# IotaWatt4_3.net
KiCad netlist of a schematic drawn in EAGLE
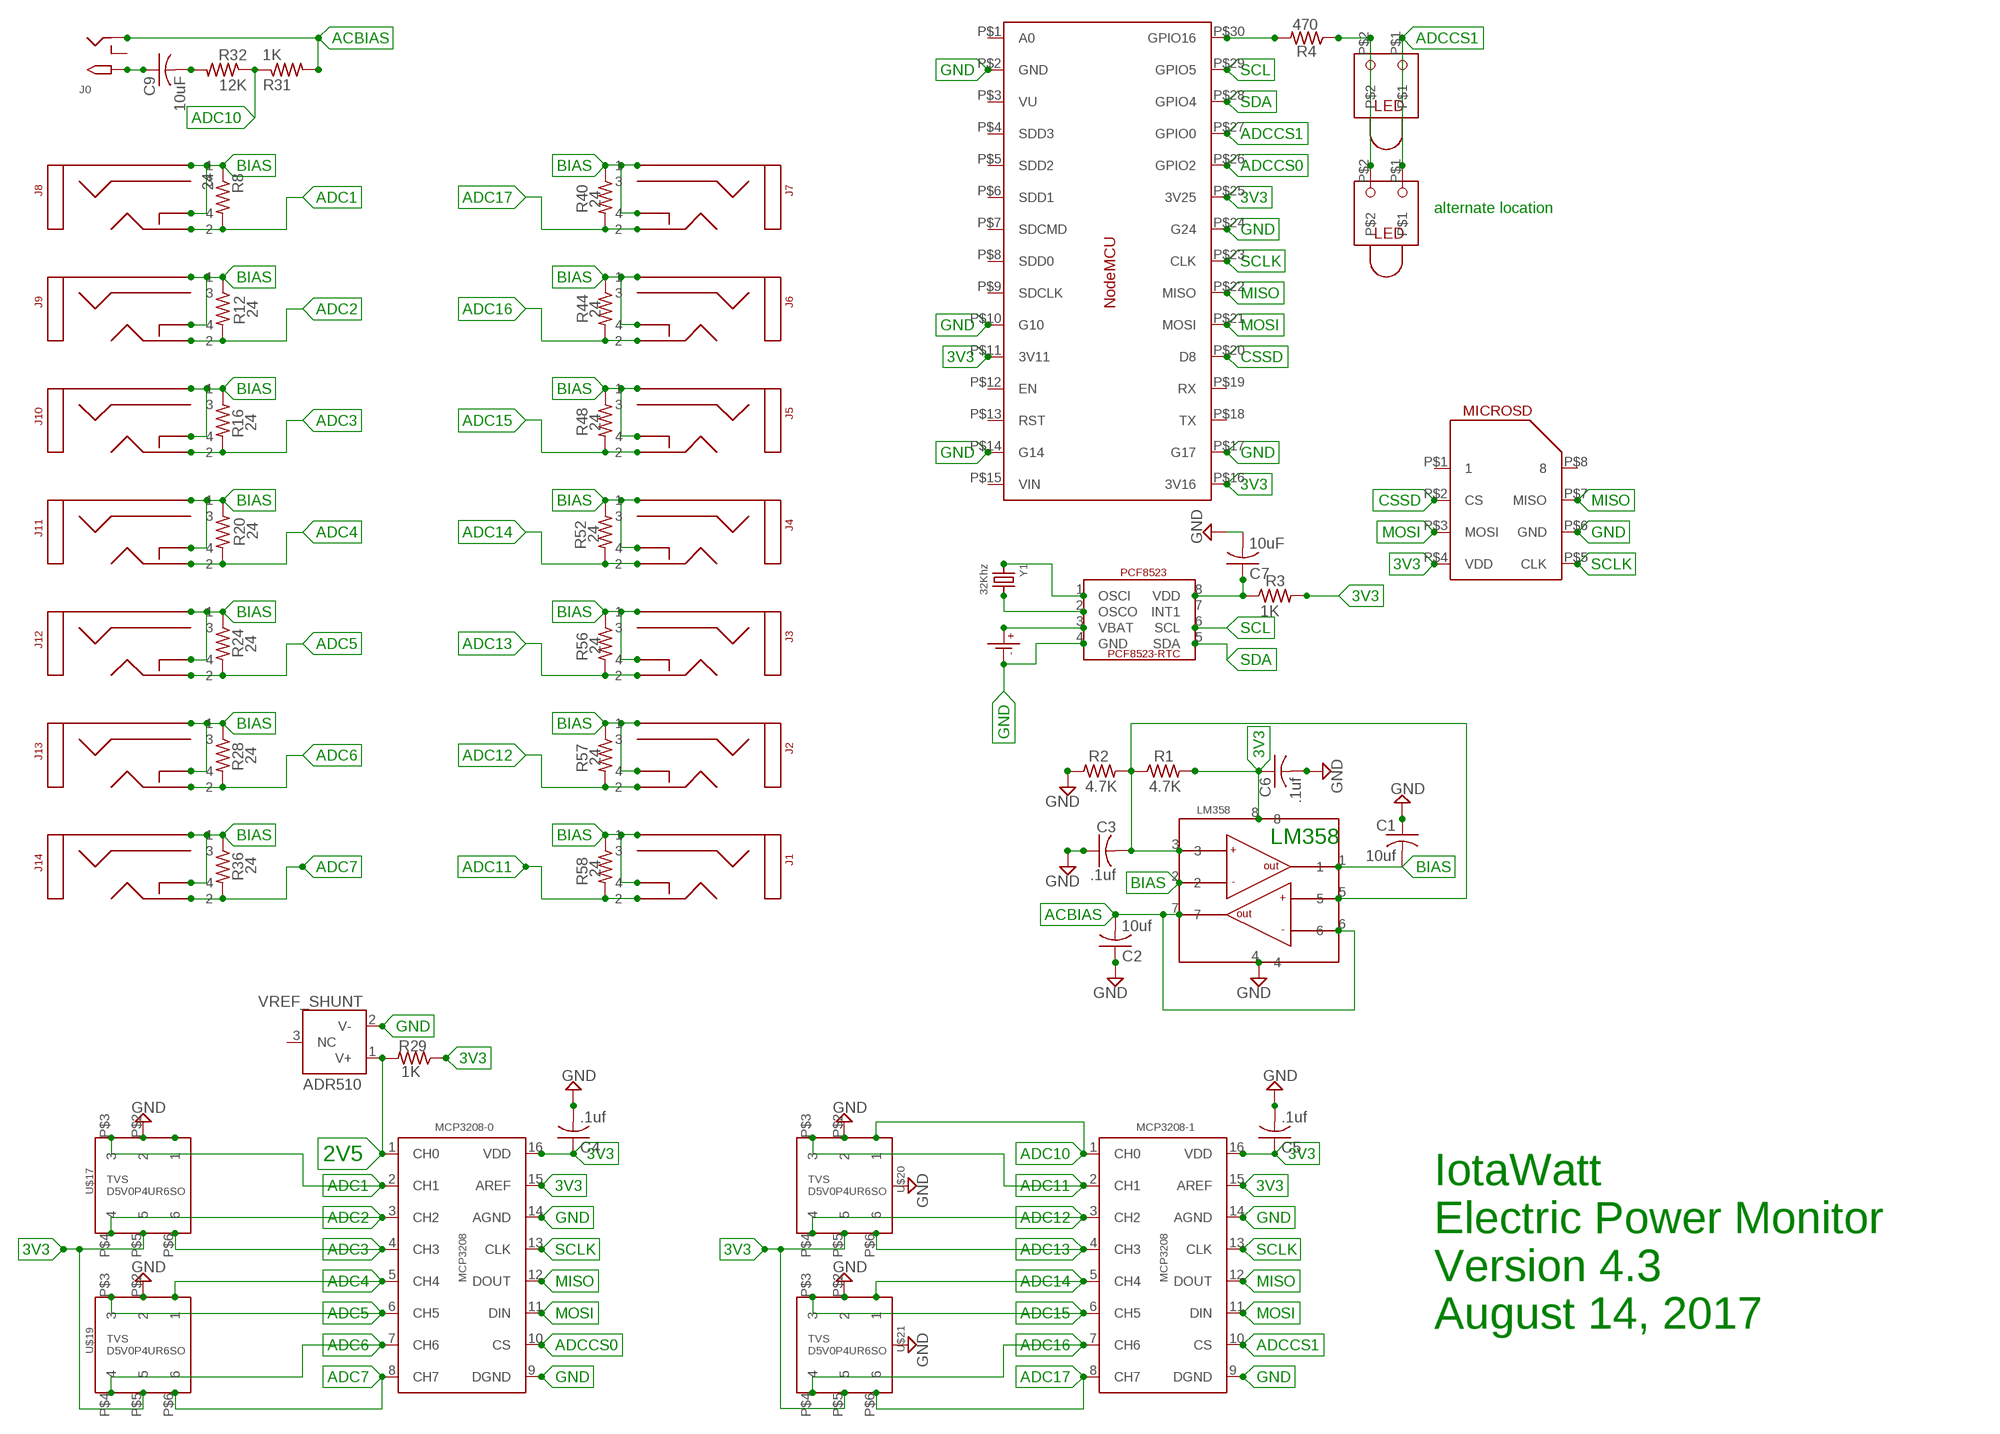
[diagram p0: schematic, sheet 1]

(export (version "E")
  (design (tool "Eeschema 10.0.6"))
  (components
    (comp (ref "ADR510")
      (value "VREF_SHUNT")
      (footprint "eagle-import:SOT23_3")
      (libsource (lib "eagle-import") (part "VREF_SHUNT"))
    )
    (comp (ref "C1")
      (value "10uf")
      (footprint "eagle-import:C0805")
      (libsource (lib "eagle-import") (part "C-USC0805"))
    )
    (comp (ref "C2")
      (value "10uf")
      (footprint "eagle-import:C0805")
      (libsource (lib "eagle-import") (part "C-USC0805"))
    )
    (comp (ref "C3")
      (value ".1uf")
      (footprint "eagle-import:C0805")
      (libsource (lib "eagle-import") (part "C-USC0805"))
    )
    (comp (ref "C4")
      (value ".1uf")
      (footprint "eagle-import:C0805")
      (libsource (lib "eagle-import") (part "C-USC0805"))
    )
    (comp (ref "C5")
      (value ".1uf")
      (footprint "eagle-import:C0805")
      (libsource (lib "eagle-import") (part "C-USC0805"))
    )
    (comp (ref "C6")
      (value ".1uf")
      (footprint "eagle-import:C0805")
      (libsource (lib "eagle-import") (part "C-USC0805"))
    )
    (comp (ref "C7")
      (value "10uF")
      (footprint "eagle-import:C0805")
      (libsource (lib "eagle-import") (part "C-USC0805"))
    )
    (comp (ref "C9")
      (value "10uF")
      (footprint "eagle-import:C0805")
      (libsource (lib "eagle-import") (part "C-USC0805"))
    )
    (comp (ref "J0")
      (value "2.1MMJACKSMT")
      (footprint "eagle-import:DCJACK_2MM_SMT")
      (libsource (lib "eagle-import") (part "2.1MMJACKSMT"))
    )
    (comp (ref "J1")
      (value "STEREO_SMD")
      (footprint "eagle-import:STEREO_SMT")
      (libsource (lib "eagle-import") (part "STEREO_SMD"))
    )
    (comp (ref "J2")
      (value "STEREO_SMD")
      (footprint "eagle-import:STEREO_SMT")
      (libsource (lib "eagle-import") (part "STEREO_SMD"))
    )
    (comp (ref "J3")
      (value "STEREO_SMD")
      (footprint "eagle-import:STEREO_SMT")
      (libsource (lib "eagle-import") (part "STEREO_SMD"))
    )
    (comp (ref "J4")
      (value "STEREO_SMD")
      (footprint "eagle-import:STEREO_SMT")
      (libsource (lib "eagle-import") (part "STEREO_SMD"))
    )
    (comp (ref "J5")
      (value "STEREO_SMD")
      (footprint "eagle-import:STEREO_SMT")
      (libsource (lib "eagle-import") (part "STEREO_SMD"))
    )
    (comp (ref "J6")
      (value "STEREO_SMD")
      (footprint "eagle-import:STEREO_SMT")
      (libsource (lib "eagle-import") (part "STEREO_SMD"))
    )
    (comp (ref "J7")
      (value "STEREO_SMD")
      (footprint "eagle-import:STEREO_SMT")
      (libsource (lib "eagle-import") (part "STEREO_SMD"))
    )
    (comp (ref "J8")
      (value "STEREO_SMD")
      (footprint "eagle-import:STEREO_SMT")
      (libsource (lib "eagle-import") (part "STEREO_SMD"))
    )
    (comp (ref "J9")
      (value "STEREO_SMD")
      (footprint "eagle-import:STEREO_SMT")
      (libsource (lib "eagle-import") (part "STEREO_SMD"))
    )
    (comp (ref "J10")
      (value "STEREO_SMD")
      (footprint "eagle-import:STEREO_SMT")
      (libsource (lib "eagle-import") (part "STEREO_SMD"))
    )
    (comp (ref "J11")
      (value "STEREO_SMD")
      (footprint "eagle-import:STEREO_SMT")
      (libsource (lib "eagle-import") (part "STEREO_SMD"))
    )
    (comp (ref "J12")
      (value "STEREO_SMD")
      (footprint "eagle-import:STEREO_SMT")
      (libsource (lib "eagle-import") (part "STEREO_SMD"))
    )
    (comp (ref "J13")
      (value "STEREO_SMD")
      (footprint "eagle-import:STEREO_SMT")
      (libsource (lib "eagle-import") (part "STEREO_SMD"))
    )
    (comp (ref "J14")
      (value "STEREO_SMD")
      (footprint "eagle-import:STEREO_SMT")
      (libsource (lib "eagle-import") (part "STEREO_SMD"))
    )
    (comp (ref "MCP3208-0")
      (value "MCP3208")
      (footprint "eagle-import:SOIC_16")
      (libsource (lib "eagle-import") (part "MCP3208"))
    )
    (comp (ref "MCP3208-1")
      (value "MCP3208")
      (footprint "eagle-import:SOIC_16")
      (libsource (lib "eagle-import") (part "MCP3208"))
    )
    (comp (ref "MICROSD")
      (value "MICROSD_PUSH/PULL")
      (footprint "eagle-import:MICROSD")
      (libsource (lib "eagle-import") (part "MICROSD_PUSH/PULL"))
    )
    (comp (ref "PCF8523")
      (value "PCF8523_RTC")
      (footprint "eagle-import:SOIC_8")
      (libsource (lib "eagle-import") (part "PCF8523_RTC"))
    )
    (comp (ref "R1")
      (value "4.7K")
      (footprint "eagle-import:R0805")
      (libsource (lib "eagle-import") (part "R-US_R0805"))
    )
    (comp (ref "R2")
      (value "4.7K")
      (footprint "eagle-import:R0805")
      (libsource (lib "eagle-import") (part "R-US_R0805"))
    )
    (comp (ref "R3")
      (value "1K")
      (footprint "eagle-import:R0805")
      (libsource (lib "eagle-import") (part "R-US_R0805"))
    )
    (comp (ref "R4")
      (value "470")
      (footprint "eagle-import:R0805")
      (libsource (lib "eagle-import") (part "R-US_R0805"))
    )
    (comp (ref "R8")
      (value "24")
      (footprint "eagle-import:R0805")
      (libsource (lib "eagle-import") (part "R-US_R0805"))
    )
    (comp (ref "R12")
      (value "24")
      (footprint "eagle-import:R0805")
      (libsource (lib "eagle-import") (part "R-US_R0805"))
    )
    (comp (ref "R16")
      (value "24")
      (footprint "eagle-import:R0805")
      (libsource (lib "eagle-import") (part "R-US_R0805"))
    )
    (comp (ref "R20")
      (value "24")
      (footprint "eagle-import:R0805")
      (libsource (lib "eagle-import") (part "R-US_R0805"))
    )
    (comp (ref "R24")
      (value "24")
      (footprint "eagle-import:R0805")
      (libsource (lib "eagle-import") (part "R-US_R0805"))
    )
    (comp (ref "R28")
      (value "24")
      (footprint "eagle-import:R0805")
      (libsource (lib "eagle-import") (part "R-US_R0805"))
    )
    (comp (ref "R29")
      (value "1K")
      (footprint "eagle-import:R0805")
      (libsource (lib "eagle-import") (part "R-US_R0805"))
    )
    (comp (ref "R31")
      (value "1K")
      (footprint "eagle-import:R0805")
      (libsource (lib "eagle-import") (part "R-US_R0805"))
    )
    (comp (ref "R32")
      (value "12K")
      (footprint "eagle-import:R0805")
      (libsource (lib "eagle-import") (part "R-US_R0805"))
    )
    (comp (ref "R36")
      (value "24")
      (footprint "eagle-import:R0805")
      (libsource (lib "eagle-import") (part "R-US_R0805"))
    )
    (comp (ref "R40")
      (value "24")
      (footprint "eagle-import:R0805")
      (libsource (lib "eagle-import") (part "R-US_R0805"))
    )
    (comp (ref "R44")
      (value "24")
      (footprint "eagle-import:R0805")
      (libsource (lib "eagle-import") (part "R-US_R0805"))
    )
    (comp (ref "R48")
      (value "24")
      (footprint "eagle-import:R0805")
      (libsource (lib "eagle-import") (part "R-US_R0805"))
    )
    (comp (ref "R52")
      (value "24")
      (footprint "eagle-import:R0805")
      (libsource (lib "eagle-import") (part "R-US_R0805"))
    )
    (comp (ref "R56")
      (value "24")
      (footprint "eagle-import:R0805")
      (libsource (lib "eagle-import") (part "R-US_R0805"))
    )
    (comp (ref "R57")
      (value "24")
      (footprint "eagle-import:R0805")
      (libsource (lib "eagle-import") (part "R-US_R0805"))
    )
    (comp (ref "R58")
      (value "24")
      (footprint "eagle-import:R0805")
      (libsource (lib "eagle-import") (part "R-US_R0805"))
    )
    (comp (ref "U$15")
      (value "LED_RT_TRH")
      (footprint "eagle-import:LED_TH_RT")
      (libsource (lib "eagle-import") (part "LED_RT_TRH"))
    )
    (comp (ref "U$16")
      (value "NODEMCU")
      (footprint "eagle-import:NODEMCU")
      (libsource (lib "eagle-import") (part "NODEMCU"))
    )
    (comp (ref "U$17")
      (value "TVS_4CHAN_ARRAYSC-74")
      (footprint "eagle-import:SC-74")
      (libsource (lib "eagle-import") (part "TVS_4CHAN_ARRAYSC-74"))
    )
    (comp (ref "U$18")
      (value "CR1220SMD")
      (footprint "eagle-import:CR1220SMD")
      (libsource (lib "eagle-import") (part "CR1220SMD"))
    )
    (comp (ref "U$19")
      (value "TVS_4CHAN_ARRAYSC-74")
      (footprint "eagle-import:SC-74")
      (libsource (lib "eagle-import") (part "TVS_4CHAN_ARRAYSC-74"))
    )
    (comp (ref "U$20")
      (value "TVS_4CHAN_ARRAYSC-74")
      (footprint "eagle-import:SC-74")
      (libsource (lib "eagle-import") (part "TVS_4CHAN_ARRAYSC-74"))
    )
    (comp (ref "U$21")
      (value "TVS_4CHAN_ARRAYSC-74")
      (footprint "eagle-import:SC-74")
      (libsource (lib "eagle-import") (part "TVS_4CHAN_ARRAYSC-74"))
    )
    (comp (ref "U$22")
      (value "LM358_DUAL_OP-AMP")
      (footprint "eagle-import:SOIC_8")
      (libsource (lib "eagle-import") (part "LM358_DUAL_OP-AMP"))
    )
    (comp (ref "U$23")
      (value "LED_RT_TRH")
      (footprint "eagle-import:LED_TH_RT")
      (libsource (lib "eagle-import") (part "LED_RT_TRH"))
    )
    (comp (ref "Y1")
      (value "32Khz")
      (footprint "eagle-import:CRYSTAL_8X3.8")
      (libsource (lib "eagle-import") (part "CRYSTAL8X3.8SMT"))
    )
  )
  (nets
    (net (code "1") (name "2V5") (class "Default")
      (node (ref "ADR510") (pin "1") (pinfunction "V+_1") (pintype "bidirectional"))
      (node (ref "MCP3208-0") (pin "1") (pinfunction "CH0_1") (pintype "input"))
      (node (ref "R29") (pin "2") (pinfunction "2_2") (pintype "passive"))
    )
    (net (code "2") (name "3V3") (class "Default")
      (node (ref "C4") (pin "1") (pinfunction "1_1") (pintype "passive"))
      (node (ref "C5") (pin "1") (pinfunction "1_1") (pintype "passive"))
      (node (ref "C6") (pin "1") (pinfunction "1_1") (pintype "passive"))
      (node (ref "MCP3208-0") (pin "15") (pinfunction "AREF_15") (pintype "input"))
      (node (ref "MCP3208-0") (pin "16") (pinfunction "VDD_16") (pintype "bidirectional"))
      (node (ref "MCP3208-1") (pin "15") (pinfunction "AREF_15") (pintype "input"))
      (node (ref "MCP3208-1") (pin "16") (pinfunction "VDD_16") (pintype "bidirectional"))
      (node (ref "MICROSD") (pin "P$4") (pinfunction "VDD_P$4") (pintype "bidirectional"))
      (node (ref "R1") (pin "2") (pinfunction "2_2") (pintype "passive"))
      (node (ref "R29") (pin "1") (pinfunction "1_1") (pintype "passive"))
      (node (ref "R3") (pin "2") (pinfunction "2_2") (pintype "passive"))
      (node (ref "U$16") (pin "P$11") (pinfunction "3V11_P$11") (pintype "bidirectional"))
      (node (ref "U$16") (pin "P$16") (pinfunction "3V16_P$16") (pintype "bidirectional"))
      (node (ref "U$16") (pin "P$25") (pinfunction "3V25_P$25") (pintype "bidirectional"))
      (node (ref "U$17") (pin "P$5") (pinfunction "5_P$5") (pintype "bidirectional"))
      (node (ref "U$19") (pin "P$5") (pinfunction "5_P$5") (pintype "bidirectional"))
      (node (ref "U$20") (pin "P$5") (pinfunction "5_P$5") (pintype "bidirectional"))
      (node (ref "U$21") (pin "P$5") (pinfunction "5_P$5") (pintype "bidirectional"))
      (node (ref "U$22") (pin "8") (pinfunction "8_8") (pintype "bidirectional"))
    )
    (net (code "3") (name "ACBIAS") (class "Default")
      (node (ref "C2") (pin "2") (pinfunction "2_2") (pintype "passive"))
      (node (ref "J0") (pin "GND") (pinfunction "RING_GND") (pintype "bidirectional"))
      (node (ref "R31") (pin "2") (pinfunction "2_2") (pintype "passive"))
      (node (ref "U$22") (pin "6") (pinfunction "6_6") (pintype "bidirectional"))
      (node (ref "U$22") (pin "7") (pinfunction "7_7") (pintype "bidirectional"))
    )
    (net (code "4") (name "ADC1") (class "Default")
      (node (ref "J8") (pin "P$2") (pinfunction "2_P$2") (pintype "bidirectional"))
      (node (ref "MCP3208-0") (pin "2") (pinfunction "CH1_2") (pintype "input"))
      (node (ref "R8") (pin "2") (pinfunction "2_2") (pintype "passive"))
      (node (ref "U$17") (pin "P$3") (pinfunction "3_P$3") (pintype "bidirectional"))
    )
    (net (code "5") (name "ADC2") (class "Default")
      (node (ref "J9") (pin "P$2") (pinfunction "2_P$2") (pintype "bidirectional"))
      (node (ref "MCP3208-0") (pin "3") (pinfunction "CH2_3") (pintype "input"))
      (node (ref "R12") (pin "2") (pinfunction "2_2") (pintype "passive"))
      (node (ref "U$17") (pin "P$4") (pinfunction "4_P$4") (pintype "bidirectional"))
    )
    (net (code "6") (name "ADC3") (class "Default")
      (node (ref "J10") (pin "P$2") (pinfunction "2_P$2") (pintype "bidirectional"))
      (node (ref "MCP3208-0") (pin "4") (pinfunction "CH3_4") (pintype "input"))
      (node (ref "R16") (pin "2") (pinfunction "2_2") (pintype "passive"))
      (node (ref "U$17") (pin "P$6") (pinfunction "6_P$6") (pintype "bidirectional"))
    )
    (net (code "7") (name "ADC4") (class "Default")
      (node (ref "J11") (pin "P$2") (pinfunction "2_P$2") (pintype "bidirectional"))
      (node (ref "MCP3208-0") (pin "5") (pinfunction "CH4_5") (pintype "bidirectional"))
      (node (ref "R20") (pin "2") (pinfunction "2_2") (pintype "passive"))
      (node (ref "U$19") (pin "P$1") (pinfunction "1_P$1") (pintype "bidirectional"))
    )
    (net (code "8") (name "ADC5") (class "Default")
      (node (ref "J12") (pin "P$2") (pinfunction "2_P$2") (pintype "bidirectional"))
      (node (ref "MCP3208-0") (pin "6") (pinfunction "CH5_6") (pintype "bidirectional"))
      (node (ref "R24") (pin "2") (pinfunction "2_2") (pintype "passive"))
      (node (ref "U$19") (pin "P$3") (pinfunction "3_P$3") (pintype "bidirectional"))
    )
    (net (code "9") (name "ADC6") (class "Default")
      (node (ref "J13") (pin "P$2") (pinfunction "2_P$2") (pintype "bidirectional"))
      (node (ref "MCP3208-0") (pin "7") (pinfunction "CH6_7") (pintype "input"))
      (node (ref "R28") (pin "2") (pinfunction "2_2") (pintype "passive"))
      (node (ref "U$19") (pin "P$4") (pinfunction "4_P$4") (pintype "bidirectional"))
    )
    (net (code "10") (name "ADC7") (class "Default")
      (node (ref "J14") (pin "P$2") (pinfunction "2_P$2") (pintype "bidirectional"))
      (node (ref "MCP3208-0") (pin "8") (pinfunction "CH7_8") (pintype "bidirectional"))
      (node (ref "R36") (pin "2") (pinfunction "2_2") (pintype "passive"))
      (node (ref "U$19") (pin "P$6") (pinfunction "6_P$6") (pintype "bidirectional"))
    )
    (net (code "11") (name "ADC10") (class "Default")
      (node (ref "MCP3208-1") (pin "1") (pinfunction "CH0_1") (pintype "input"))
      (node (ref "R31") (pin "1") (pinfunction "1_1") (pintype "passive"))
      (node (ref "R32") (pin "1") (pinfunction "1_1") (pintype "passive"))
      (node (ref "U$20") (pin "P$1") (pinfunction "1_P$1") (pintype "bidirectional"))
    )
    (net (code "12") (name "ADC11") (class "Default")
      (node (ref "J1") (pin "P$2") (pinfunction "2_P$2") (pintype "bidirectional"))
      (node (ref "MCP3208-1") (pin "2") (pinfunction "CH1_2") (pintype "input"))
      (node (ref "R58") (pin "2") (pinfunction "2_2") (pintype "passive"))
      (node (ref "U$20") (pin "P$3") (pinfunction "3_P$3") (pintype "bidirectional"))
    )
    (net (code "13") (name "ADC12") (class "Default")
      (node (ref "J2") (pin "P$2") (pinfunction "2_P$2") (pintype "bidirectional"))
      (node (ref "MCP3208-1") (pin "3") (pinfunction "CH2_3") (pintype "input"))
      (node (ref "R57") (pin "2") (pinfunction "2_2") (pintype "passive"))
      (node (ref "U$20") (pin "P$4") (pinfunction "4_P$4") (pintype "bidirectional"))
    )
    (net (code "14") (name "ADC13") (class "Default")
      (node (ref "J3") (pin "P$2") (pinfunction "2_P$2") (pintype "bidirectional"))
      (node (ref "MCP3208-1") (pin "4") (pinfunction "CH3_4") (pintype "input"))
      (node (ref "R56") (pin "2") (pinfunction "2_2") (pintype "passive"))
      (node (ref "U$20") (pin "P$6") (pinfunction "6_P$6") (pintype "bidirectional"))
    )
    (net (code "15") (name "ADC14") (class "Default")
      (node (ref "J4") (pin "P$2") (pinfunction "2_P$2") (pintype "bidirectional"))
      (node (ref "MCP3208-1") (pin "5") (pinfunction "CH4_5") (pintype "bidirectional"))
      (node (ref "R52") (pin "2") (pinfunction "2_2") (pintype "passive"))
      (node (ref "U$21") (pin "P$1") (pinfunction "1_P$1") (pintype "bidirectional"))
    )
    (net (code "16") (name "ADC15") (class "Default")
      (node (ref "J5") (pin "P$2") (pinfunction "2_P$2") (pintype "bidirectional"))
      (node (ref "MCP3208-1") (pin "6") (pinfunction "CH5_6") (pintype "bidirectional"))
      (node (ref "R48") (pin "2") (pinfunction "2_2") (pintype "passive"))
      (node (ref "U$21") (pin "P$3") (pinfunction "3_P$3") (pintype "bidirectional"))
    )
    (net (code "17") (name "ADC16") (class "Default")
      (node (ref "J6") (pin "P$2") (pinfunction "2_P$2") (pintype "bidirectional"))
      (node (ref "MCP3208-1") (pin "7") (pinfunction "CH6_7") (pintype "input"))
      (node (ref "R44") (pin "2") (pinfunction "2_2") (pintype "passive"))
      (node (ref "U$21") (pin "P$4") (pinfunction "4_P$4") (pintype "bidirectional"))
    )
    (net (code "18") (name "ADC17") (class "Default")
      (node (ref "J7") (pin "P$2") (pinfunction "2_P$2") (pintype "bidirectional"))
      (node (ref "MCP3208-1") (pin "8") (pinfunction "CH7_8") (pintype "bidirectional"))
      (node (ref "R40") (pin "2") (pinfunction "2_2") (pintype "passive"))
      (node (ref "U$21") (pin "P$6") (pinfunction "6_P$6") (pintype "bidirectional"))
    )
    (net (code "19") (name "ADCCS0") (class "Default")
      (node (ref "MCP3208-0") (pin "10") (pinfunction "CS_10") (pintype "input"))
      (node (ref "U$16") (pin "P$26") (pinfunction "GPIO2_P$26") (pintype "bidirectional"))
    )
    (net (code "20") (name "ADCCS1") (class "Default")
      (node (ref "MCP3208-1") (pin "10") (pinfunction "CS_10") (pintype "input"))
      (node (ref "U$15") (pin "P$1") (pinfunction "P$1_P$1") (pintype "bidirectional"))
      (node (ref "U$16") (pin "P$27") (pinfunction "GPIO0_P$27") (pintype "bidirectional"))
      (node (ref "U$23") (pin "P$1") (pinfunction "P$1_P$1") (pintype "bidirectional"))
    )
    (net (code "21") (name "BIAS") (class "Default")
      (node (ref "C1") (pin "2") (pinfunction "2_2") (pintype "passive"))
      (node (ref "J1") (pin "P$1") (pinfunction "1_P$1") (pintype "bidirectional"))
      (node (ref "J1") (pin "P$4") (pinfunction "4_P$4") (pintype "bidirectional"))
      (node (ref "J10") (pin "P$1") (pinfunction "1_P$1") (pintype "bidirectional"))
      (node (ref "J10") (pin "P$4") (pinfunction "4_P$4") (pintype "bidirectional"))
      (node (ref "J11") (pin "P$1") (pinfunction "1_P$1") (pintype "bidirectional"))
      (node (ref "J11") (pin "P$4") (pinfunction "4_P$4") (pintype "bidirectional"))
      (node (ref "J12") (pin "P$1") (pinfunction "1_P$1") (pintype "bidirectional"))
      (node (ref "J12") (pin "P$4") (pinfunction "4_P$4") (pintype "bidirectional"))
      (node (ref "J13") (pin "P$1") (pinfunction "1_P$1") (pintype "bidirectional"))
      (node (ref "J13") (pin "P$4") (pinfunction "4_P$4") (pintype "bidirectional"))
      (node (ref "J14") (pin "P$1") (pinfunction "1_P$1") (pintype "bidirectional"))
      (node (ref "J14") (pin "P$4") (pinfunction "4_P$4") (pintype "bidirectional"))
      (node (ref "J2") (pin "P$1") (pinfunction "1_P$1") (pintype "bidirectional"))
      (node (ref "J2") (pin "P$4") (pinfunction "4_P$4") (pintype "bidirectional"))
      (node (ref "J3") (pin "P$1") (pinfunction "1_P$1") (pintype "bidirectional"))
      (node (ref "J3") (pin "P$4") (pinfunction "4_P$4") (pintype "bidirectional"))
      (node (ref "J4") (pin "P$1") (pinfunction "1_P$1") (pintype "bidirectional"))
      (node (ref "J4") (pin "P$4") (pinfunction "4_P$4") (pintype "bidirectional"))
      (node (ref "J5") (pin "P$1") (pinfunction "1_P$1") (pintype "bidirectional"))
      (node (ref "J5") (pin "P$4") (pinfunction "4_P$4") (pintype "bidirectional"))
      (node (ref "J6") (pin "P$1") (pinfunction "1_P$1") (pintype "bidirectional"))
      (node (ref "J6") (pin "P$4") (pinfunction "4_P$4") (pintype "bidirectional"))
      (node (ref "J7") (pin "P$1") (pinfunction "1_P$1") (pintype "bidirectional"))
      (node (ref "J7") (pin "P$4") (pinfunction "4_P$4") (pintype "bidirectional"))
      (node (ref "J8") (pin "P$1") (pinfunction "1_P$1") (pintype "bidirectional"))
      (node (ref "J8") (pin "P$4") (pinfunction "4_P$4") (pintype "bidirectional"))
      (node (ref "J9") (pin "P$1") (pinfunction "1_P$1") (pintype "bidirectional"))
      (node (ref "J9") (pin "P$4") (pinfunction "4_P$4") (pintype "bidirectional"))
      (node (ref "R12") (pin "1") (pinfunction "1_1") (pintype "passive"))
      (node (ref "R16") (pin "1") (pinfunction "1_1") (pintype "passive"))
      (node (ref "R20") (pin "1") (pinfunction "1_1") (pintype "passive"))
      (node (ref "R24") (pin "1") (pinfunction "1_1") (pintype "passive"))
      (node (ref "R28") (pin "1") (pinfunction "1_1") (pintype "passive"))
      (node (ref "R36") (pin "1") (pinfunction "1_1") (pintype "passive"))
      (node (ref "R40") (pin "1") (pinfunction "1_1") (pintype "passive"))
      (node (ref "R44") (pin "1") (pinfunction "1_1") (pintype "passive"))
      (node (ref "R48") (pin "1") (pinfunction "1_1") (pintype "passive"))
      (node (ref "R52") (pin "1") (pinfunction "1_1") (pintype "passive"))
      (node (ref "R56") (pin "1") (pinfunction "1_1") (pintype "passive"))
      (node (ref "R57") (pin "1") (pinfunction "1_1") (pintype "passive"))
      (node (ref "R58") (pin "1") (pinfunction "1_1") (pintype "passive"))
      (node (ref "R8") (pin "1") (pinfunction "1_1") (pintype "passive"))
      (node (ref "U$22") (pin "1") (pinfunction "1_1") (pintype "bidirectional"))
      (node (ref "U$22") (pin "2") (pinfunction "2_2") (pintype "bidirectional"))
    )
    (net (code "22") (name "CSSD") (class "Default")
      (node (ref "MICROSD") (pin "P$2") (pinfunction "CS_P$2") (pintype "bidirectional"))
      (node (ref "U$16") (pin "P$20") (pinfunction "D8_P$20") (pintype "bidirectional"))
    )
    (net (code "23") (name "GND") (class "Default")
      (node (ref "ADR510") (pin "2") (pinfunction "V-_2") (pintype "bidirectional"))
      (node (ref "C1") (pin "1") (pinfunction "1_1") (pintype "passive"))
      (node (ref "C2") (pin "1") (pinfunction "1_1") (pintype "passive"))
      (node (ref "C3") (pin "1") (pinfunction "1_1") (pintype "passive"))
      (node (ref "C4") (pin "2") (pinfunction "2_2") (pintype "passive"))
      (node (ref "C5") (pin "2") (pinfunction "2_2") (pintype "passive"))
      (node (ref "C6") (pin "2") (pinfunction "2_2") (pintype "passive"))
      (node (ref "C7") (pin "2") (pinfunction "2_2") (pintype "passive"))
      (node (ref "MCP3208-0") (pin "14") (pinfunction "AGND_14") (pintype "input"))
      (node (ref "MCP3208-0") (pin "9") (pinfunction "DGND_9") (pintype "bidirectional"))
      (node (ref "MCP3208-1") (pin "14") (pinfunction "AGND_14") (pintype "input"))
      (node (ref "MCP3208-1") (pin "9") (pinfunction "DGND_9") (pintype "bidirectional"))
      (node (ref "MICROSD") (pin "P$6") (pinfunction "GND_P$6") (pintype "bidirectional"))
      (node (ref "PCF8523") (pin "4") (pinfunction "GND_4") (pintype "bidirectional"))
      (node (ref "R2") (pin "1") (pinfunction "1_1") (pintype "passive"))
      (node (ref "U$16") (pin "P$10") (pinfunction "G10_P$10") (pintype "bidirectional"))
      (node (ref "U$16") (pin "P$14") (pinfunction "G14_P$14") (pintype "bidirectional"))
      (node (ref "U$16") (pin "P$17") (pinfunction "G17_P$17") (pintype "bidirectional"))
      (node (ref "U$16") (pin "P$2") (pinfunction "GND_P$2") (pintype "bidirectional"))
      (node (ref "U$16") (pin "P$24") (pinfunction "G24_P$24") (pintype "bidirectional"))
      (node (ref "U$17") (pin "P$2") (pinfunction "2_P$2") (pintype "bidirectional"))
      (node (ref "U$18") (pin "P-") (pinfunction "P$-_P-") (pintype "bidirectional"))
      (node (ref "U$19") (pin "P$2") (pinfunction "2_P$2") (pintype "bidirectional"))
      (node (ref "U$20") (pin "P$2") (pinfunction "2_P$2") (pintype "bidirectional"))
      (node (ref "U$21") (pin "P$2") (pinfunction "2_P$2") (pintype "bidirectional"))
      (node (ref "U$22") (pin "4") (pinfunction "4_4") (pintype "bidirectional"))
    )
    (net (code "24") (name "MISO") (class "Default")
      (node (ref "MCP3208-0") (pin "12") (pinfunction "DOUT_12") (pintype "bidirectional"))
      (node (ref "MCP3208-1") (pin "12") (pinfunction "DOUT_12") (pintype "bidirectional"))
      (node (ref "MICROSD") (pin "P$7") (pinfunction "MISO_P$7") (pintype "bidirectional"))
      (node (ref "U$16") (pin "P$22") (pinfunction "MISO_P$22") (pintype "bidirectional"))
    )
    (net (code "25") (name "MOSI") (class "Default")
      (node (ref "MCP3208-0") (pin "11") (pinfunction "DIN_11") (pintype "input"))
      (node (ref "MCP3208-1") (pin "11") (pinfunction "DIN_11") (pintype "input"))
      (node (ref "MICROSD") (pin "P$3") (pinfunction "MOSI_P$3") (pintype "bidirectional"))
      (node (ref "U$16") (pin "P$21") (pinfunction "MOSI_P$21") (pintype "bidirectional"))
    )
    (net (code "26") (name "Net-(C3-Pad2)") (class "Default")
      (node (ref "C3") (pin "2") (pinfunction "2_2") (pintype "passive"))
      (node (ref "R1") (pin "1") (pinfunction "1_1") (pintype "passive"))
      (node (ref "R2") (pin "2") (pinfunction "2_2") (pintype "passive"))
      (node (ref "U$22") (pin "3") (pinfunction "3_3") (pintype "bidirectional"))
      (node (ref "U$22") (pin "5") (pinfunction "5_5") (pintype "bidirectional"))
    )
    (net (code "27") (name "Net-(C9-Pad2)") (class "Default")
      (node (ref "C9") (pin "2") (pinfunction "2_2") (pintype "passive"))
      (node (ref "R32") (pin "2") (pinfunction "2_2") (pintype "passive"))
    )
    (net (code "28") (name "Net-(J0-TIP)") (class "Default")
      (node (ref "C9") (pin "1") (pinfunction "1_1") (pintype "passive"))
      (node (ref "J0") (pin "PWR2") (pinfunction "TIP_PWR2") (pintype "bidirectional"))
    )
    (net (code "29") (name "Net-(PCF8523-OSCI)") (class "Default")
      (node (ref "PCF8523") (pin "1") (pinfunction "OSCI_1") (pintype "bidirectional"))
      (node (ref "Y1") (pin "P$1") (pinfunction "1_P$1") (pintype "passive"))
    )
    (net (code "30") (name "Net-(PCF8523-OSCO)") (class "Default")
      (node (ref "PCF8523") (pin "2") (pinfunction "OSCO_2") (pintype "bidirectional"))
      (node (ref "Y1") (pin "P$4") (pinfunction "2_P$4") (pintype "passive"))
    )
    (net (code "31") (name "Net-(PCF8523-VBAT)") (class "Default")
      (node (ref "PCF8523") (pin "3") (pinfunction "VBAT_3") (pintype "bidirectional"))
      (node (ref "U$18") (pin "P+") (pinfunction "P$+_P+") (pintype "bidirectional"))
    )
    (net (code "32") (name "Net-(PCF8523-VDD)") (class "Default")
      (node (ref "C7") (pin "1") (pinfunction "1_1") (pintype "passive"))
      (node (ref "PCF8523") (pin "8") (pinfunction "VDD_8") (pintype "bidirectional"))
      (node (ref "R3") (pin "1") (pinfunction "1_1") (pintype "passive"))
    )
    (net (code "33") (name "Net-(R4-Pad1)") (class "Default")
      (node (ref "R4") (pin "1") (pinfunction "1_1") (pintype "passive"))
      (node (ref "U$15") (pin "P$2") (pinfunction "P$2_P$2") (pintype "bidirectional"))
      (node (ref "U$23") (pin "P$2") (pinfunction "P$2_P$2") (pintype "bidirectional"))
    )
    (net (code "34") (name "Net-(U$16-GPIO16)") (class "Default")
      (node (ref "R4") (pin "2") (pinfunction "2_2") (pintype "passive"))
      (node (ref "U$16") (pin "P$30") (pinfunction "GPIO16_P$30") (pintype "bidirectional"))
    )
    (net (code "35") (name "SCL") (class "Default")
      (node (ref "PCF8523") (pin "6") (pinfunction "SCL_6") (pintype "bidirectional"))
      (node (ref "U$16") (pin "P$29") (pinfunction "GPIO5_P$29") (pintype "bidirectional"))
    )
    (net (code "36") (name "SCLK") (class "Default")
      (node (ref "MCP3208-0") (pin "13") (pinfunction "CLK_13") (pintype "input"))
      (node (ref "MCP3208-1") (pin "13") (pinfunction "CLK_13") (pintype "input"))
      (node (ref "MICROSD") (pin "P$5") (pinfunction "CLK_P$5") (pintype "bidirectional"))
      (node (ref "U$16") (pin "P$23") (pinfunction "CLK_P$23") (pintype "bidirectional"))
    )
    (net (code "37") (name "SDA") (class "Default")
      (node (ref "PCF8523") (pin "5") (pinfunction "SDA_5") (pintype "bidirectional"))
      (node (ref "U$16") (pin "P$28") (pinfunction "GPIO4_P$28") (pintype "bidirectional"))
    )
    (net (code "38") (name "unconnected-(ADR510-NC-Pad3)") (class "Default")
      (node (ref "ADR510") (pin "3") (pinfunction "NC_3") (pintype "bidirectional"))
    )
    (net (code "39") (name "unconnected-(J0-RING_SW-PadGNDBREAK)") (class "Default")
      (node (ref "J0") (pin "GNDBREAK") (pinfunction "RING_SW_GNDBREAK") (pintype "bidirectional"))
    )
    (net (code "40") (name "unconnected-(J1-3-PadP$3)") (class "Default")
      (node (ref "J1") (pin "P$3") (pinfunction "3_P$3") (pintype "bidirectional"))
    )
    (net (code "41") (name "unconnected-(J2-3-PadP$3)") (class "Default")
      (node (ref "J2") (pin "P$3") (pinfunction "3_P$3") (pintype "bidirectional"))
    )
    (net (code "42") (name "unconnected-(J3-3-PadP$3)") (class "Default")
      (node (ref "J3") (pin "P$3") (pinfunction "3_P$3") (pintype "bidirectional"))
    )
    (net (code "43") (name "unconnected-(J4-3-PadP$3)") (class "Default")
      (node (ref "J4") (pin "P$3") (pinfunction "3_P$3") (pintype "bidirectional"))
    )
    (net (code "44") (name "unconnected-(J5-3-PadP$3)") (class "Default")
      (node (ref "J5") (pin "P$3") (pinfunction "3_P$3") (pintype "bidirectional"))
    )
    (net (code "45") (name "unconnected-(J6-3-PadP$3)") (class "Default")
      (node (ref "J6") (pin "P$3") (pinfunction "3_P$3") (pintype "bidirectional"))
    )
    (net (code "46") (name "unconnected-(J7-3-PadP$3)") (class "Default")
      (node (ref "J7") (pin "P$3") (pinfunction "3_P$3") (pintype "bidirectional"))
    )
    (net (code "47") (name "unconnected-(J8-3-PadP$3)") (class "Default")
      (node (ref "J8") (pin "P$3") (pinfunction "3_P$3") (pintype "bidirectional"))
    )
    (net (code "48") (name "unconnected-(J9-3-PadP$3)") (class "Default")
      (node (ref "J9") (pin "P$3") (pinfunction "3_P$3") (pintype "bidirectional"))
    )
    (net (code "49") (name "unconnected-(J10-3-PadP$3)") (class "Default")
      (node (ref "J10") (pin "P$3") (pinfunction "3_P$3") (pintype "bidirectional"))
    )
    (net (code "50") (name "unconnected-(J11-3-PadP$3)") (class "Default")
      (node (ref "J11") (pin "P$3") (pinfunction "3_P$3") (pintype "bidirectional"))
    )
    (net (code "51") (name "unconnected-(J12-3-PadP$3)") (class "Default")
      (node (ref "J12") (pin "P$3") (pinfunction "3_P$3") (pintype "bidirectional"))
    )
    (net (code "52") (name "unconnected-(J13-3-PadP$3)") (class "Default")
      (node (ref "J13") (pin "P$3") (pinfunction "3_P$3") (pintype "bidirectional"))
    )
    (net (code "53") (name "unconnected-(J14-3-PadP$3)") (class "Default")
      (node (ref "J14") (pin "P$3") (pinfunction "3_P$3") (pintype "bidirectional"))
    )
    (net (code "54") (name "unconnected-(MICROSD-1-PadP$1)") (class "Default")
      (node (ref "MICROSD") (pin "P$1") (pinfunction "1_P$1") (pintype "bidirectional"))
    )
    (net (code "55") (name "unconnected-(MICROSD-8-PadP$8)") (class "Default")
      (node (ref "MICROSD") (pin "P$8") (pinfunction "8_P$8") (pintype "bidirectional"))
    )
    (net (code "56") (name "unconnected-(PCF8523-INT1-Pad7)") (class "Default")
      (node (ref "PCF8523") (pin "7") (pinfunction "INT1_7") (pintype "bidirectional"))
    )
    (net (code "57") (name "unconnected-(U$16-A0-PadP$1)") (class "Default")
      (node (ref "U$16") (pin "P$1") (pinfunction "A0_P$1") (pintype "bidirectional"))
    )
    (net (code "58") (name "unconnected-(U$16-EN-PadP$12)") (class "Default")
      (node (ref "U$16") (pin "P$12") (pinfunction "EN_P$12") (pintype "bidirectional"))
    )
    (net (code "59") (name "unconnected-(U$16-RST-PadP$13)") (class "Default")
      (node (ref "U$16") (pin "P$13") (pinfunction "RST_P$13") (pintype "bidirectional"))
    )
    (net (code "60") (name "unconnected-(U$16-RX-PadP$19)") (class "Default")
      (node (ref "U$16") (pin "P$19") (pinfunction "RX_P$19") (pintype "bidirectional"))
    )
    (net (code "61") (name "unconnected-(U$16-SDCLK-PadP$9)") (class "Default")
      (node (ref "U$16") (pin "P$9") (pinfunction "SDCLK_P$9") (pintype "bidirectional"))
    )
    (net (code "62") (name "unconnected-(U$16-SDCMD-PadP$7)") (class "Default")
      (node (ref "U$16") (pin "P$7") (pinfunction "SDCMD_P$7") (pintype "bidirectional"))
    )
    (net (code "63") (name "unconnected-(U$16-SDD0-PadP$8)") (class "Default")
      (node (ref "U$16") (pin "P$8") (pinfunction "SDD0_P$8") (pintype "bidirectional"))
    )
    (net (code "64") (name "unconnected-(U$16-SDD1-PadP$6)") (class "Default")
      (node (ref "U$16") (pin "P$6") (pinfunction "SDD1_P$6") (pintype "bidirectional"))
    )
    (net (code "65") (name "unconnected-(U$16-SDD2-PadP$5)") (class "Default")
      (node (ref "U$16") (pin "P$5") (pinfunction "SDD2_P$5") (pintype "bidirectional"))
    )
    (net (code "66") (name "unconnected-(U$16-SDD3-PadP$4)") (class "Default")
      (node (ref "U$16") (pin "P$4") (pinfunction "SDD3_P$4") (pintype "bidirectional"))
    )
    (net (code "67") (name "unconnected-(U$16-TX-PadP$18)") (class "Default")
      (node (ref "U$16") (pin "P$18") (pinfunction "TX_P$18") (pintype "bidirectional"))
    )
    (net (code "68") (name "unconnected-(U$16-VIN-PadP$15)") (class "Default")
      (node (ref "U$16") (pin "P$15") (pinfunction "VIN_P$15") (pintype "bidirectional"))
    )
    (net (code "69") (name "unconnected-(U$16-VU-PadP$3)") (class "Default")
      (node (ref "U$16") (pin "P$3") (pinfunction "VU_P$3") (pintype "bidirectional"))
    )
    (net (code "70") (name "unconnected-(U$17-1-PadP$1)") (class "Default")
      (node (ref "U$17") (pin "P$1") (pinfunction "1_P$1") (pintype "bidirectional"))
    )
  )
)
